# MR01.net
KiCad netlist of a schematic drawn in EAGLE
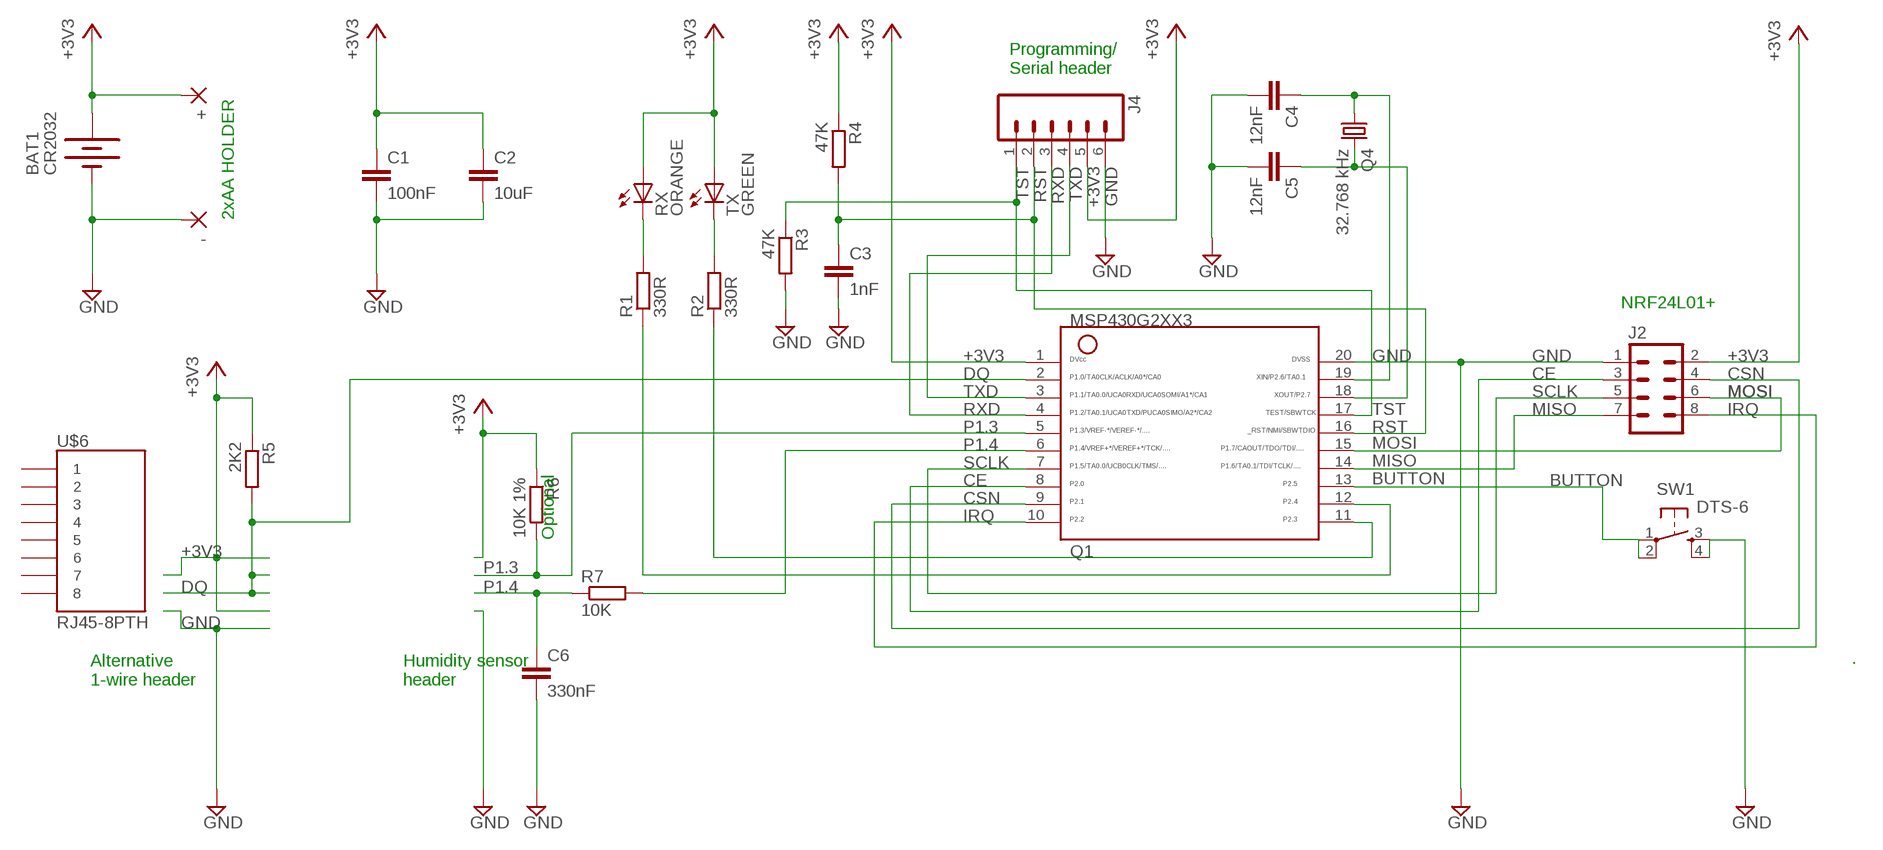
[diagram p0: schematic, sheet 1]

(export (version "E")
  (design (tool "Eeschema 10.0.6"))
  (components
    (comp (ref "+")
      (value "2,54/1,0")
      (footprint "eagle-import:2,54_1,0")
      (libsource (lib "eagle-import") (part "2,54/1,0"))
    )
    (comp (ref "-")
      (value "2,54/1,0")
      (footprint "eagle-import:2,54_1,0")
      (libsource (lib "eagle-import") (part "2,54/1,0"))
    )
    (comp (ref "BAT1")
      (value "CR2032")
      (footprint "eagle-import:BATTCOM_20MM_PTH")
      (libsource (lib "eagle-import") (part "BATTERY20PTH"))
    )
    (comp (ref "C1")
      (value "100nF")
      (footprint "eagle-import:C0805")
      (libsource (lib "eagle-import") (part "resistor_C-EUC0805"))
    )
    (comp (ref "C2")
      (value "10uF")
      (footprint "eagle-import:C1206")
      (libsource (lib "eagle-import") (part "C-EUC1206"))
    )
    (comp (ref "C3")
      (value "1nF")
      (footprint "eagle-import:C0805")
      (libsource (lib "eagle-import") (part "resistor_C-EUC0805"))
    )
    (comp (ref "C4")
      (value "12nF")
      (footprint "eagle-import:C0805")
      (libsource (lib "eagle-import") (part "resistor_C-EUC0805"))
    )
    (comp (ref "C5")
      (value "12nF")
      (footprint "eagle-import:C0805")
      (libsource (lib "eagle-import") (part "resistor_C-EUC0805"))
    )
    (comp (ref "C6")
      (value "330nF")
      (footprint "eagle-import:C0805")
      (libsource (lib "eagle-import") (part "resistor_C-EUC0805"))
    )
    (comp (ref "J2")
      (value "M04X2")
      (footprint "eagle-import:2X4")
      (libsource (lib "eagle-import") (part "M04X2"))
    )
    (comp (ref "J4")
      (value "M06SIP")
      (footprint "eagle-import:1X06")
      (libsource (lib "eagle-import") (part "M06SIP"))
    )
    (comp (ref "Q1")
      (value "G2XX3---PW20")
      (footprint "eagle-import:PW20")
      (libsource (lib "eagle-import") (part "G2XX3---PW20"))
    )
    (comp (ref "Q4")
      (value "32.768 kHz")
      (footprint "eagle-import:TC38H")
      (libsource (lib "eagle-import") (part "CRYSTALTC38H"))
    )
    (comp (ref "R1")
      (value "330R")
      (footprint "eagle-import:M0805")
      (fields (field (name "RESISTANCE") "4K7"))
      (libsource (lib "eagle-import") (part "R-EU_M0805"))
    )
    (comp (ref "R2")
      (value "330R")
      (footprint "eagle-import:M0805")
      (fields (field (name "RESISTANCE") "4K7"))
      (libsource (lib "eagle-import") (part "R-EU_M0805"))
    )
    (comp (ref "R3")
      (value "47K")
      (footprint "eagle-import:M0805")
      (fields (field (name "RESISTANCE") "4K7"))
      (libsource (lib "eagle-import") (part "R-EU_M0805"))
    )
    (comp (ref "R4")
      (value "47K")
      (footprint "eagle-import:M0805")
      (fields (field (name "RESISTANCE") "4K7"))
      (libsource (lib "eagle-import") (part "R-EU_M0805"))
    )
    (comp (ref "R5")
      (value "2K2")
      (footprint "eagle-import:M0805")
      (fields (field (name "RESISTANCE") "4K7"))
      (libsource (lib "eagle-import") (part "R-EU_M0805"))
    )
    (comp (ref "R6")
      (value "10K 1%")
      (footprint "eagle-import:M0805")
      (fields (field (name "RESISTANCE") "4K7"))
      (libsource (lib "eagle-import") (part "R-EU_M0805"))
    )
    (comp (ref "R7")
      (value "10K")
      (footprint "eagle-import:M0805")
      (fields (field (name "RESISTANCE") "4K7"))
      (libsource (lib "eagle-import") (part "R-EU_M0805"))
    )
    (comp (ref "RX")
      (value "ORANGE")
      (footprint "eagle-import:CHIPLED_0805")
      (libsource (lib "eagle-import") (part "LEDCHIPLED_0805"))
    )
    (comp (ref "SW1")
      (value "DTS-6")
      (footprint "eagle-import:DTS-6")
      (libsource (lib "eagle-import") (part "DTS-6"))
    )
    (comp (ref "TX")
      (value "GREEN")
      (footprint "eagle-import:CHIPLED_0805")
      (libsource (lib "eagle-import") (part "LEDCHIPLED_0805"))
    )
    (comp (ref "U$6")
      (value "RJ45-8PTH")
      (footprint "eagle-import:RJ45-8")
      (libsource (lib "eagle-import") (part "RJ45-8PTH"))
    )
  )
  (nets
    (net (code "1") (name "+3V3") (class "Default")
      (node (ref "+") (pin "1") (pinfunction "P_1") (pintype "passive"))
      (node (ref "BAT1") (pin "1") (pinfunction "+_1") (pintype "power_in"))
      (node (ref "C1") (pin "1") (pinfunction "1_1") (pintype "passive"))
      (node (ref "C2") (pin "1") (pinfunction "1_1") (pintype "passive"))
      (node (ref "J2") (pin "2") (pinfunction "2_2") (pintype "passive"))
      (node (ref "J4") (pin "5") (pinfunction "5_5") (pintype "passive"))
      (node (ref "Q1") (pin "1") (pinfunction "1_1") (pintype "bidirectional"))
      (node (ref "R4") (pin "1") (pinfunction "1_1") (pintype "passive"))
      (node (ref "R5") (pin "1") (pinfunction "1_1") (pintype "passive"))
      (node (ref "R6") (pin "1") (pinfunction "1_1") (pintype "passive"))
      (node (ref "RX") (pin "A") (pinfunction "A_A") (pintype "passive"))
      (node (ref "TX") (pin "A") (pinfunction "A_A") (pintype "passive"))
    )
    (net (code "2") (name "/BUTTON") (class "Default")
      (node (ref "Q1") (pin "13") (pinfunction "13_13") (pintype "bidirectional"))
      (node (ref "SW1") (pin "1") (pinfunction "1_1") (pintype "passive"))
      (node (ref "SW1") (pin "2") (pinfunction "2_2") (pintype "passive"))
    )
    (net (code "3") (name "/CE") (class "Default")
      (node (ref "J2") (pin "3") (pinfunction "3_3") (pintype "passive"))
      (node (ref "Q1") (pin "8") (pinfunction "8_8") (pintype "bidirectional"))
    )
    (net (code "4") (name "/CSN") (class "Default")
      (node (ref "J2") (pin "4") (pinfunction "4_4") (pintype "passive"))
      (node (ref "Q1") (pin "9") (pinfunction "9_9") (pintype "bidirectional"))
    )
    (net (code "5") (name "/DQ") (class "Default")
      (node (ref "Q1") (pin "2") (pinfunction "2_2") (pintype "bidirectional"))
      (node (ref "R5") (pin "2") (pinfunction "2_2") (pintype "passive"))
    )
    (net (code "6") (name "/IRQ") (class "Default")
      (node (ref "J2") (pin "8") (pinfunction "8_8") (pintype "passive"))
      (node (ref "Q1") (pin "10") (pinfunction "10_10") (pintype "bidirectional"))
    )
    (net (code "7") (name "/MISO") (class "Default")
      (node (ref "J2") (pin "7") (pinfunction "7_7") (pintype "passive"))
      (node (ref "Q1") (pin "14") (pinfunction "14_14") (pintype "bidirectional"))
    )
    (net (code "8") (name "/MOSI") (class "Default")
      (node (ref "J2") (pin "6") (pinfunction "6_6") (pintype "passive"))
      (node (ref "Q1") (pin "15") (pinfunction "15_15") (pintype "bidirectional"))
    )
    (net (code "9") (name "/P1.3") (class "Default")
      (node (ref "Q1") (pin "5") (pinfunction "5_5") (pintype "bidirectional"))
      (node (ref "R6") (pin "2") (pinfunction "2_2") (pintype "passive"))
    )
    (net (code "10") (name "/P1.4") (class "Default")
      (node (ref "Q1") (pin "6") (pinfunction "6_6") (pintype "bidirectional"))
      (node (ref "R7") (pin "2") (pinfunction "2_2") (pintype "passive"))
    )
    (net (code "11") (name "/RST") (class "Default")
      (node (ref "C3") (pin "1") (pinfunction "1_1") (pintype "passive"))
      (node (ref "J4") (pin "2") (pinfunction "2_2") (pintype "passive"))
      (node (ref "Q1") (pin "16") (pinfunction "16_16") (pintype "bidirectional"))
      (node (ref "R4") (pin "2") (pinfunction "2_2") (pintype "passive"))
    )
    (net (code "12") (name "/RXD") (class "Default")
      (node (ref "J4") (pin "3") (pinfunction "3_3") (pintype "passive"))
      (node (ref "Q1") (pin "4") (pinfunction "4_4") (pintype "bidirectional"))
    )
    (net (code "13") (name "/SCLK") (class "Default")
      (node (ref "J2") (pin "5") (pinfunction "5_5") (pintype "passive"))
      (node (ref "Q1") (pin "7") (pinfunction "7_7") (pintype "bidirectional"))
    )
    (net (code "14") (name "/TST") (class "Default")
      (node (ref "J4") (pin "1") (pinfunction "1_1") (pintype "passive"))
      (node (ref "Q1") (pin "17") (pinfunction "17_17") (pintype "bidirectional"))
      (node (ref "R3") (pin "1") (pinfunction "1_1") (pintype "passive"))
    )
    (net (code "15") (name "/TXD") (class "Default")
      (node (ref "J4") (pin "4") (pinfunction "4_4") (pintype "passive"))
      (node (ref "Q1") (pin "3") (pinfunction "3_3") (pintype "bidirectional"))
    )
    (net (code "16") (name "GND") (class "Default")
      (node (ref "-") (pin "1") (pinfunction "P_1") (pintype "passive"))
      (node (ref "BAT1") (pin "2") (pinfunction "-_2") (pintype "power_in"))
      (node (ref "C1") (pin "2") (pinfunction "2_2") (pintype "passive"))
      (node (ref "C2") (pin "2") (pinfunction "2_2") (pintype "passive"))
      (node (ref "C3") (pin "2") (pinfunction "2_2") (pintype "passive"))
      (node (ref "C4") (pin "2") (pinfunction "2_2") (pintype "passive"))
      (node (ref "C5") (pin "2") (pinfunction "2_2") (pintype "passive"))
      (node (ref "C6") (pin "2") (pinfunction "2_2") (pintype "passive"))
      (node (ref "J2") (pin "1") (pinfunction "1_1") (pintype "passive"))
      (node (ref "J4") (pin "6") (pinfunction "6_6") (pintype "passive"))
      (node (ref "Q1") (pin "20") (pinfunction "20_20") (pintype "bidirectional"))
      (node (ref "R3") (pin "2") (pinfunction "2_2") (pintype "passive"))
      (node (ref "SW1") (pin "3") (pinfunction "3_3") (pintype "passive"))
      (node (ref "SW1") (pin "4") (pinfunction "4_4") (pintype "passive"))
    )
    (net (code "17") (name "Net-(C4-Pad1)") (class "Default")
      (node (ref "C4") (pin "1") (pinfunction "1_1") (pintype "passive"))
      (node (ref "Q1") (pin "19") (pinfunction "19_19") (pintype "bidirectional"))
      (node (ref "Q4") (pin "1") (pinfunction "1_1") (pintype "passive"))
    )
    (net (code "18") (name "Net-(C5-Pad1)") (class "Default")
      (node (ref "C5") (pin "1") (pinfunction "1_1") (pintype "passive"))
      (node (ref "Q1") (pin "18") (pinfunction "18_18") (pintype "bidirectional"))
      (node (ref "Q4") (pin "2") (pinfunction "2_2") (pintype "passive"))
    )
    (net (code "19") (name "Net-(C6-Pad1)") (class "Default")
      (node (ref "C6") (pin "1") (pinfunction "1_1") (pintype "passive"))
      (node (ref "R7") (pin "1") (pinfunction "1_1") (pintype "passive"))
    )
    (net (code "20") (name "Net-(Q1-Pad11)") (class "Default")
      (node (ref "Q1") (pin "11") (pinfunction "11_11") (pintype "bidirectional"))
      (node (ref "R2") (pin "1") (pinfunction "1_1") (pintype "passive"))
    )
    (net (code "21") (name "Net-(Q1-Pad12)") (class "Default")
      (node (ref "Q1") (pin "12") (pinfunction "12_12") (pintype "bidirectional"))
      (node (ref "R1") (pin "1") (pinfunction "1_1") (pintype "passive"))
    )
    (net (code "22") (name "Net-(R1-Pad2)") (class "Default")
      (node (ref "R1") (pin "2") (pinfunction "2_2") (pintype "passive"))
      (node (ref "RX") (pin "C") (pinfunction "C_C") (pintype "passive"))
    )
    (net (code "23") (name "Net-(R2-Pad2)") (class "Default")
      (node (ref "R2") (pin "2") (pinfunction "2_2") (pintype "passive"))
      (node (ref "TX") (pin "C") (pinfunction "C_C") (pintype "passive"))
    )
    (net (code "24") (name "unconnected-(U$6-Pad1)") (class "Default")
      (node (ref "U$6") (pin "1") (pinfunction "1_1") (pintype "bidirectional"))
    )
    (net (code "25") (name "unconnected-(U$6-Pad2)") (class "Default")
      (node (ref "U$6") (pin "2") (pinfunction "2_2") (pintype "bidirectional"))
    )
    (net (code "26") (name "unconnected-(U$6-Pad3)") (class "Default")
      (node (ref "U$6") (pin "3") (pinfunction "3_3") (pintype "bidirectional"))
    )
    (net (code "27") (name "unconnected-(U$6-Pad4)") (class "Default")
      (node (ref "U$6") (pin "4") (pinfunction "4_4") (pintype "bidirectional"))
    )
    (net (code "28") (name "unconnected-(U$6-Pad5)") (class "Default")
      (node (ref "U$6") (pin "5") (pinfunction "5_5") (pintype "bidirectional"))
    )
    (net (code "29") (name "unconnected-(U$6-Pad6)") (class "Default")
      (node (ref "U$6") (pin "6") (pinfunction "6_6") (pintype "bidirectional"))
    )
    (net (code "30") (name "unconnected-(U$6-Pad7)") (class "Default")
      (node (ref "U$6") (pin "7") (pinfunction "7_7") (pintype "bidirectional"))
    )
    (net (code "31") (name "unconnected-(U$6-Pad8)") (class "Default")
      (node (ref "U$6") (pin "8") (pinfunction "8_8") (pintype "bidirectional"))
    )
  )
)
